# mass_measurement.net
KiCad netlist of a schematic drawn in EAGLE
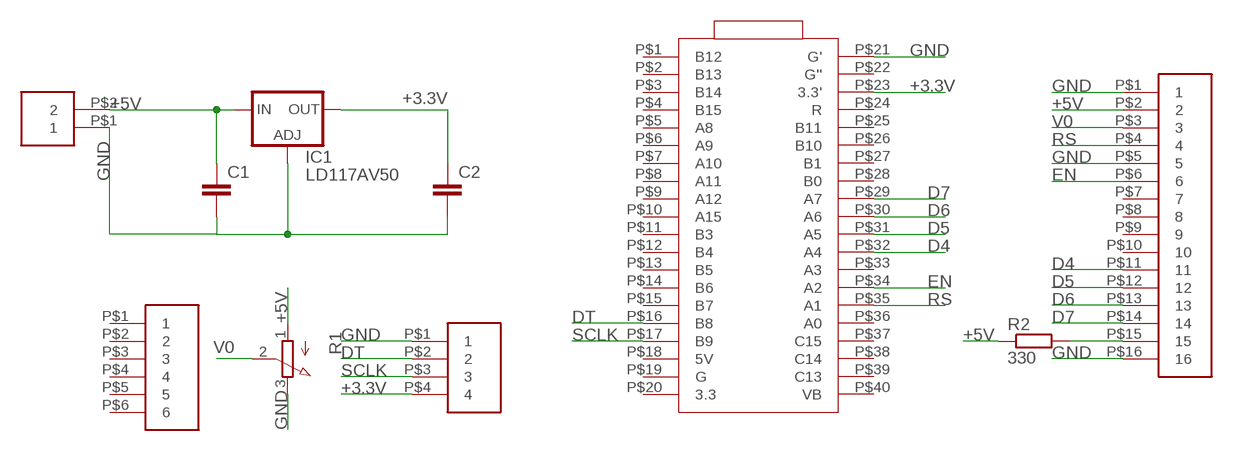
[diagram p0: schematic, sheet 1]

(export (version "E")
  (design (tool "Eeschema 10.0.6"))
  (components
    (comp (ref "C1")
      (value "C-EU025-030X050")
      (footprint "eagle-import:C025-030X050")
      (libsource (lib "eagle-import") (part "C-EU025-030X050"))
    )
    (comp (ref "C2")
      (value "C-EU025-030X050")
      (footprint "eagle-import:C025-030X050")
      (libsource (lib "eagle-import") (part "C-EU025-030X050"))
    )
    (comp (ref "IC1")
      (value "LD117AV50")
      (footprint "eagle-import:TO220L1")
      (libsource (lib "eagle-import") (part "LD117A?V50"))
    )
    (comp (ref "R1")
      (value "3RP/1610N")
      (footprint "eagle-import:3RP_1610N")
      (libsource (lib "eagle-import") (part "3RP/1610N"))
    )
    (comp (ref "R2")
      (value "330")
      (footprint "eagle-import:0617_17")
      (libsource (lib "eagle-import") (part "R-EU_0617/17"))
    )
    (comp (ref "U$1")
      (value "HEADER_2")
      (footprint "eagle-import:HEADER_2_FOOT")
      (libsource (lib "eagle-import") (part "HEADER_2"))
    )
    (comp (ref "U$2")
      (value "HEADER_16")
      (footprint "eagle-import:HEADER_16_FOOT")
      (libsource (lib "eagle-import") (part "HEADER_16"))
    )
    (comp (ref "U$3")
      (value "BLUE_PILL_EA")
      (footprint "eagle-import:BLUE_PILL_FOOT")
      (libsource (lib "eagle-import") (part "BLUE_PILL_EA"))
    )
    (comp (ref "U$4")
      (value "HEADER_4")
      (footprint "eagle-import:HEADER_4_FOOT")
      (libsource (lib "eagle-import") (part "HEADER_4"))
    )
    (comp (ref "U$5")
      (value "HEADER_6")
      (footprint "eagle-import:HEADER_6_FOOT")
      (libsource (lib "eagle-import") (part "HEADER_6"))
    )
  )
  (nets
    (net (code "1") (name "/+3.3V") (class "Default")
      (node (ref "C2") (pin "1") (pinfunction "1_1") (pintype "passive"))
      (node (ref "IC1") (pin "2") (pinfunction "OUT_2") (pintype "passive"))
      (node (ref "U$3") (pin "P$23") (pinfunction "3.3'_P$23") (pintype "bidirectional"))
      (node (ref "U$4") (pin "P$4") (pinfunction "4_P$4") (pintype "bidirectional"))
    )
    (net (code "2") (name "/+5V") (class "Default")
      (node (ref "C1") (pin "1") (pinfunction "1_1") (pintype "passive"))
      (node (ref "IC1") (pin "3") (pinfunction "IN_3") (pintype "input"))
      (node (ref "R1") (pin "1") (pinfunction "A_1") (pintype "passive"))
      (node (ref "R2") (pin "1") (pinfunction "1_1") (pintype "passive"))
      (node (ref "U$1") (pin "P$2") (pinfunction "2_P$2") (pintype "bidirectional"))
      (node (ref "U$2") (pin "P$2") (pinfunction "2_P$2") (pintype "bidirectional"))
    )
    (net (code "3") (name "/D4") (class "Default")
      (node (ref "U$2") (pin "P$11") (pinfunction "11_P$11") (pintype "bidirectional"))
      (node (ref "U$3") (pin "P$32") (pinfunction "A4_P$32") (pintype "bidirectional"))
    )
    (net (code "4") (name "/D5") (class "Default")
      (node (ref "U$2") (pin "P$12") (pinfunction "12_P$12") (pintype "bidirectional"))
      (node (ref "U$3") (pin "P$31") (pinfunction "A5_P$31") (pintype "bidirectional"))
    )
    (net (code "5") (name "/D6") (class "Default")
      (node (ref "U$2") (pin "P$13") (pinfunction "13_P$13") (pintype "bidirectional"))
      (node (ref "U$3") (pin "P$30") (pinfunction "A6_P$30") (pintype "bidirectional"))
    )
    (net (code "6") (name "/D7") (class "Default")
      (node (ref "U$2") (pin "P$14") (pinfunction "14_P$14") (pintype "bidirectional"))
      (node (ref "U$3") (pin "P$29") (pinfunction "A7_P$29") (pintype "bidirectional"))
    )
    (net (code "7") (name "/DT") (class "Default")
      (node (ref "U$3") (pin "P$16") (pinfunction "B8_P$16") (pintype "bidirectional"))
      (node (ref "U$4") (pin "P$2") (pinfunction "2_P$2") (pintype "bidirectional"))
    )
    (net (code "8") (name "/EN") (class "Default")
      (node (ref "U$2") (pin "P$6") (pinfunction "6_P$6") (pintype "bidirectional"))
      (node (ref "U$3") (pin "P$34") (pinfunction "A2_P$34") (pintype "bidirectional"))
    )
    (net (code "9") (name "/GND") (class "Default")
      (node (ref "C1") (pin "2") (pinfunction "2_2") (pintype "passive"))
      (node (ref "C2") (pin "2") (pinfunction "2_2") (pintype "passive"))
      (node (ref "IC1") (pin "1") (pinfunction "ADJ_1") (pintype "input"))
      (node (ref "R1") (pin "3") (pinfunction "E_3") (pintype "passive"))
      (node (ref "U$1") (pin "P$1") (pinfunction "1_P$1") (pintype "bidirectional"))
      (node (ref "U$2") (pin "P$1") (pinfunction "1_P$1") (pintype "bidirectional"))
      (node (ref "U$2") (pin "P$16") (pinfunction "16_P$16") (pintype "bidirectional"))
      (node (ref "U$2") (pin "P$5") (pinfunction "5_P$5") (pintype "bidirectional"))
      (node (ref "U$3") (pin "P$21") (pinfunction "G'_P$21") (pintype "bidirectional"))
      (node (ref "U$4") (pin "P$1") (pinfunction "1_P$1") (pintype "bidirectional"))
    )
    (net (code "10") (name "/RS") (class "Default")
      (node (ref "U$2") (pin "P$4") (pinfunction "4_P$4") (pintype "bidirectional"))
      (node (ref "U$3") (pin "P$35") (pinfunction "A1_P$35") (pintype "bidirectional"))
    )
    (net (code "11") (name "/SCLK") (class "Default")
      (node (ref "U$3") (pin "P$17") (pinfunction "B9_P$17") (pintype "bidirectional"))
      (node (ref "U$4") (pin "P$3") (pinfunction "3_P$3") (pintype "bidirectional"))
    )
    (net (code "12") (name "/V0") (class "Default")
      (node (ref "R1") (pin "2") (pinfunction "S_2") (pintype "passive"))
      (node (ref "U$2") (pin "P$3") (pinfunction "3_P$3") (pintype "bidirectional"))
    )
    (net (code "13") (name "Net-(U$2-15)") (class "Default")
      (node (ref "R2") (pin "2") (pinfunction "2_2") (pintype "passive"))
      (node (ref "U$2") (pin "P$15") (pinfunction "15_P$15") (pintype "bidirectional"))
    )
    (net (code "14") (name "unconnected-(U$2-7-PadP$7)") (class "Default")
      (node (ref "U$2") (pin "P$7") (pinfunction "7_P$7") (pintype "bidirectional"))
    )
    (net (code "15") (name "unconnected-(U$2-8-PadP$8)") (class "Default")
      (node (ref "U$2") (pin "P$8") (pinfunction "8_P$8") (pintype "bidirectional"))
    )
    (net (code "16") (name "unconnected-(U$2-9-PadP$9)") (class "Default")
      (node (ref "U$2") (pin "P$9") (pinfunction "9_P$9") (pintype "bidirectional"))
    )
    (net (code "17") (name "unconnected-(U$2-10-PadP$10)") (class "Default")
      (node (ref "U$2") (pin "P$10") (pinfunction "10_P$10") (pintype "bidirectional"))
    )
    (net (code "18") (name "unconnected-(U$3-3.3-PadP$20)") (class "Default")
      (node (ref "U$3") (pin "P$20") (pinfunction "3.3_P$20") (pintype "bidirectional"))
    )
    (net (code "19") (name "unconnected-(U$3-5V-PadP$18)") (class "Default")
      (node (ref "U$3") (pin "P$18") (pinfunction "5V_P$18") (pintype "bidirectional"))
    )
    (net (code "20") (name "unconnected-(U$3-A0-PadP$36)") (class "Default")
      (node (ref "U$3") (pin "P$36") (pinfunction "A0_P$36") (pintype "bidirectional"))
    )
    (net (code "21") (name "unconnected-(U$3-A3-PadP$33)") (class "Default")
      (node (ref "U$3") (pin "P$33") (pinfunction "A3_P$33") (pintype "bidirectional"))
    )
    (net (code "22") (name "unconnected-(U$3-A8-PadP$5)") (class "Default")
      (node (ref "U$3") (pin "P$5") (pinfunction "A8_P$5") (pintype "bidirectional"))
    )
    (net (code "23") (name "unconnected-(U$3-A9-PadP$6)") (class "Default")
      (node (ref "U$3") (pin "P$6") (pinfunction "A9_P$6") (pintype "bidirectional"))
    )
    (net (code "24") (name "unconnected-(U$3-A10-PadP$7)") (class "Default")
      (node (ref "U$3") (pin "P$7") (pinfunction "A10_P$7") (pintype "bidirectional"))
    )
    (net (code "25") (name "unconnected-(U$3-A11-PadP$8)") (class "Default")
      (node (ref "U$3") (pin "P$8") (pinfunction "A11_P$8") (pintype "bidirectional"))
    )
    (net (code "26") (name "unconnected-(U$3-A12-PadP$9)") (class "Default")
      (node (ref "U$3") (pin "P$9") (pinfunction "A12_P$9") (pintype "bidirectional"))
    )
    (net (code "27") (name "unconnected-(U$3-A15-PadP$10)") (class "Default")
      (node (ref "U$3") (pin "P$10") (pinfunction "A15_P$10") (pintype "bidirectional"))
    )
    (net (code "28") (name "unconnected-(U$3-B0-PadP$28)") (class "Default")
      (node (ref "U$3") (pin "P$28") (pinfunction "B0_P$28") (pintype "bidirectional"))
    )
    (net (code "29") (name "unconnected-(U$3-B1-PadP$27)") (class "Default")
      (node (ref "U$3") (pin "P$27") (pinfunction "B1_P$27") (pintype "bidirectional"))
    )
    (net (code "30") (name "unconnected-(U$3-B3-PadP$11)") (class "Default")
      (node (ref "U$3") (pin "P$11") (pinfunction "B3_P$11") (pintype "bidirectional"))
    )
    (net (code "31") (name "unconnected-(U$3-B4-PadP$12)") (class "Default")
      (node (ref "U$3") (pin "P$12") (pinfunction "B4_P$12") (pintype "bidirectional"))
    )
    (net (code "32") (name "unconnected-(U$3-B5-PadP$13)") (class "Default")
      (node (ref "U$3") (pin "P$13") (pinfunction "B5_P$13") (pintype "bidirectional"))
    )
    (net (code "33") (name "unconnected-(U$3-B6-PadP$14)") (class "Default")
      (node (ref "U$3") (pin "P$14") (pinfunction "B6_P$14") (pintype "bidirectional"))
    )
    (net (code "34") (name "unconnected-(U$3-B7-PadP$15)") (class "Default")
      (node (ref "U$3") (pin "P$15") (pinfunction "B7_P$15") (pintype "bidirectional"))
    )
    (net (code "35") (name "unconnected-(U$3-B10-PadP$26)") (class "Default")
      (node (ref "U$3") (pin "P$26") (pinfunction "B10_P$26") (pintype "bidirectional"))
    )
    (net (code "36") (name "unconnected-(U$3-B11-PadP$25)") (class "Default")
      (node (ref "U$3") (pin "P$25") (pinfunction "B11_P$25") (pintype "bidirectional"))
    )
    (net (code "37") (name "unconnected-(U$3-B12-PadP$1)") (class "Default")
      (node (ref "U$3") (pin "P$1") (pinfunction "B12_P$1") (pintype "bidirectional"))
    )
    (net (code "38") (name "unconnected-(U$3-B13-PadP$2)") (class "Default")
      (node (ref "U$3") (pin "P$2") (pinfunction "B13_P$2") (pintype "bidirectional"))
    )
    (net (code "39") (name "unconnected-(U$3-B14-PadP$3)") (class "Default")
      (node (ref "U$3") (pin "P$3") (pinfunction "B14_P$3") (pintype "bidirectional"))
    )
    (net (code "40") (name "unconnected-(U$3-B15-PadP$4)") (class "Default")
      (node (ref "U$3") (pin "P$4") (pinfunction "B15_P$4") (pintype "bidirectional"))
    )
    (net (code "41") (name "unconnected-(U$3-C13-PadP$39)") (class "Default")
      (node (ref "U$3") (pin "P$39") (pinfunction "C13_P$39") (pintype "bidirectional"))
    )
    (net (code "42") (name "unconnected-(U$3-C14-PadP$38)") (class "Default")
      (node (ref "U$3") (pin "P$38") (pinfunction "C14_P$38") (pintype "bidirectional"))
    )
    (net (code "43") (name "unconnected-(U$3-C15-PadP$37)") (class "Default")
      (node (ref "U$3") (pin "P$37") (pinfunction "C15_P$37") (pintype "bidirectional"))
    )
    (net (code "44") (name "unconnected-(U$3-G''-PadP$22)") (class "Default")
      (node (ref "U$3") (pin "P$22") (pinfunction "G''_P$22") (pintype "bidirectional"))
    )
    (net (code "45") (name "unconnected-(U$3-G-PadP$19)") (class "Default")
      (node (ref "U$3") (pin "P$19") (pinfunction "G_P$19") (pintype "bidirectional"))
    )
    (net (code "46") (name "unconnected-(U$3-R-PadP$24)") (class "Default")
      (node (ref "U$3") (pin "P$24") (pinfunction "R_P$24") (pintype "bidirectional"))
    )
    (net (code "47") (name "unconnected-(U$3-VB-PadP$40)") (class "Default")
      (node (ref "U$3") (pin "P$40") (pinfunction "VB_P$40") (pintype "bidirectional"))
    )
    (net (code "48") (name "unconnected-(U$5-1-PadP$1)") (class "Default")
      (node (ref "U$5") (pin "P$1") (pinfunction "1_P$1") (pintype "bidirectional"))
    )
    (net (code "49") (name "unconnected-(U$5-2-PadP$2)") (class "Default")
      (node (ref "U$5") (pin "P$2") (pinfunction "2_P$2") (pintype "bidirectional"))
    )
    (net (code "50") (name "unconnected-(U$5-3-PadP$3)") (class "Default")
      (node (ref "U$5") (pin "P$3") (pinfunction "3_P$3") (pintype "bidirectional"))
    )
    (net (code "51") (name "unconnected-(U$5-4-PadP$4)") (class "Default")
      (node (ref "U$5") (pin "P$4") (pinfunction "4_P$4") (pintype "bidirectional"))
    )
    (net (code "52") (name "unconnected-(U$5-5-PadP$5)") (class "Default")
      (node (ref "U$5") (pin "P$5") (pinfunction "5_P$5") (pintype "bidirectional"))
    )
    (net (code "53") (name "unconnected-(U$5-6-PadP$6)") (class "Default")
      (node (ref "U$5") (pin "P$6") (pinfunction "6_P$6") (pintype "bidirectional"))
    )
  )
)
